# motherboard_cp2.net
KiCad netlist of a schematic drawn in EAGLE
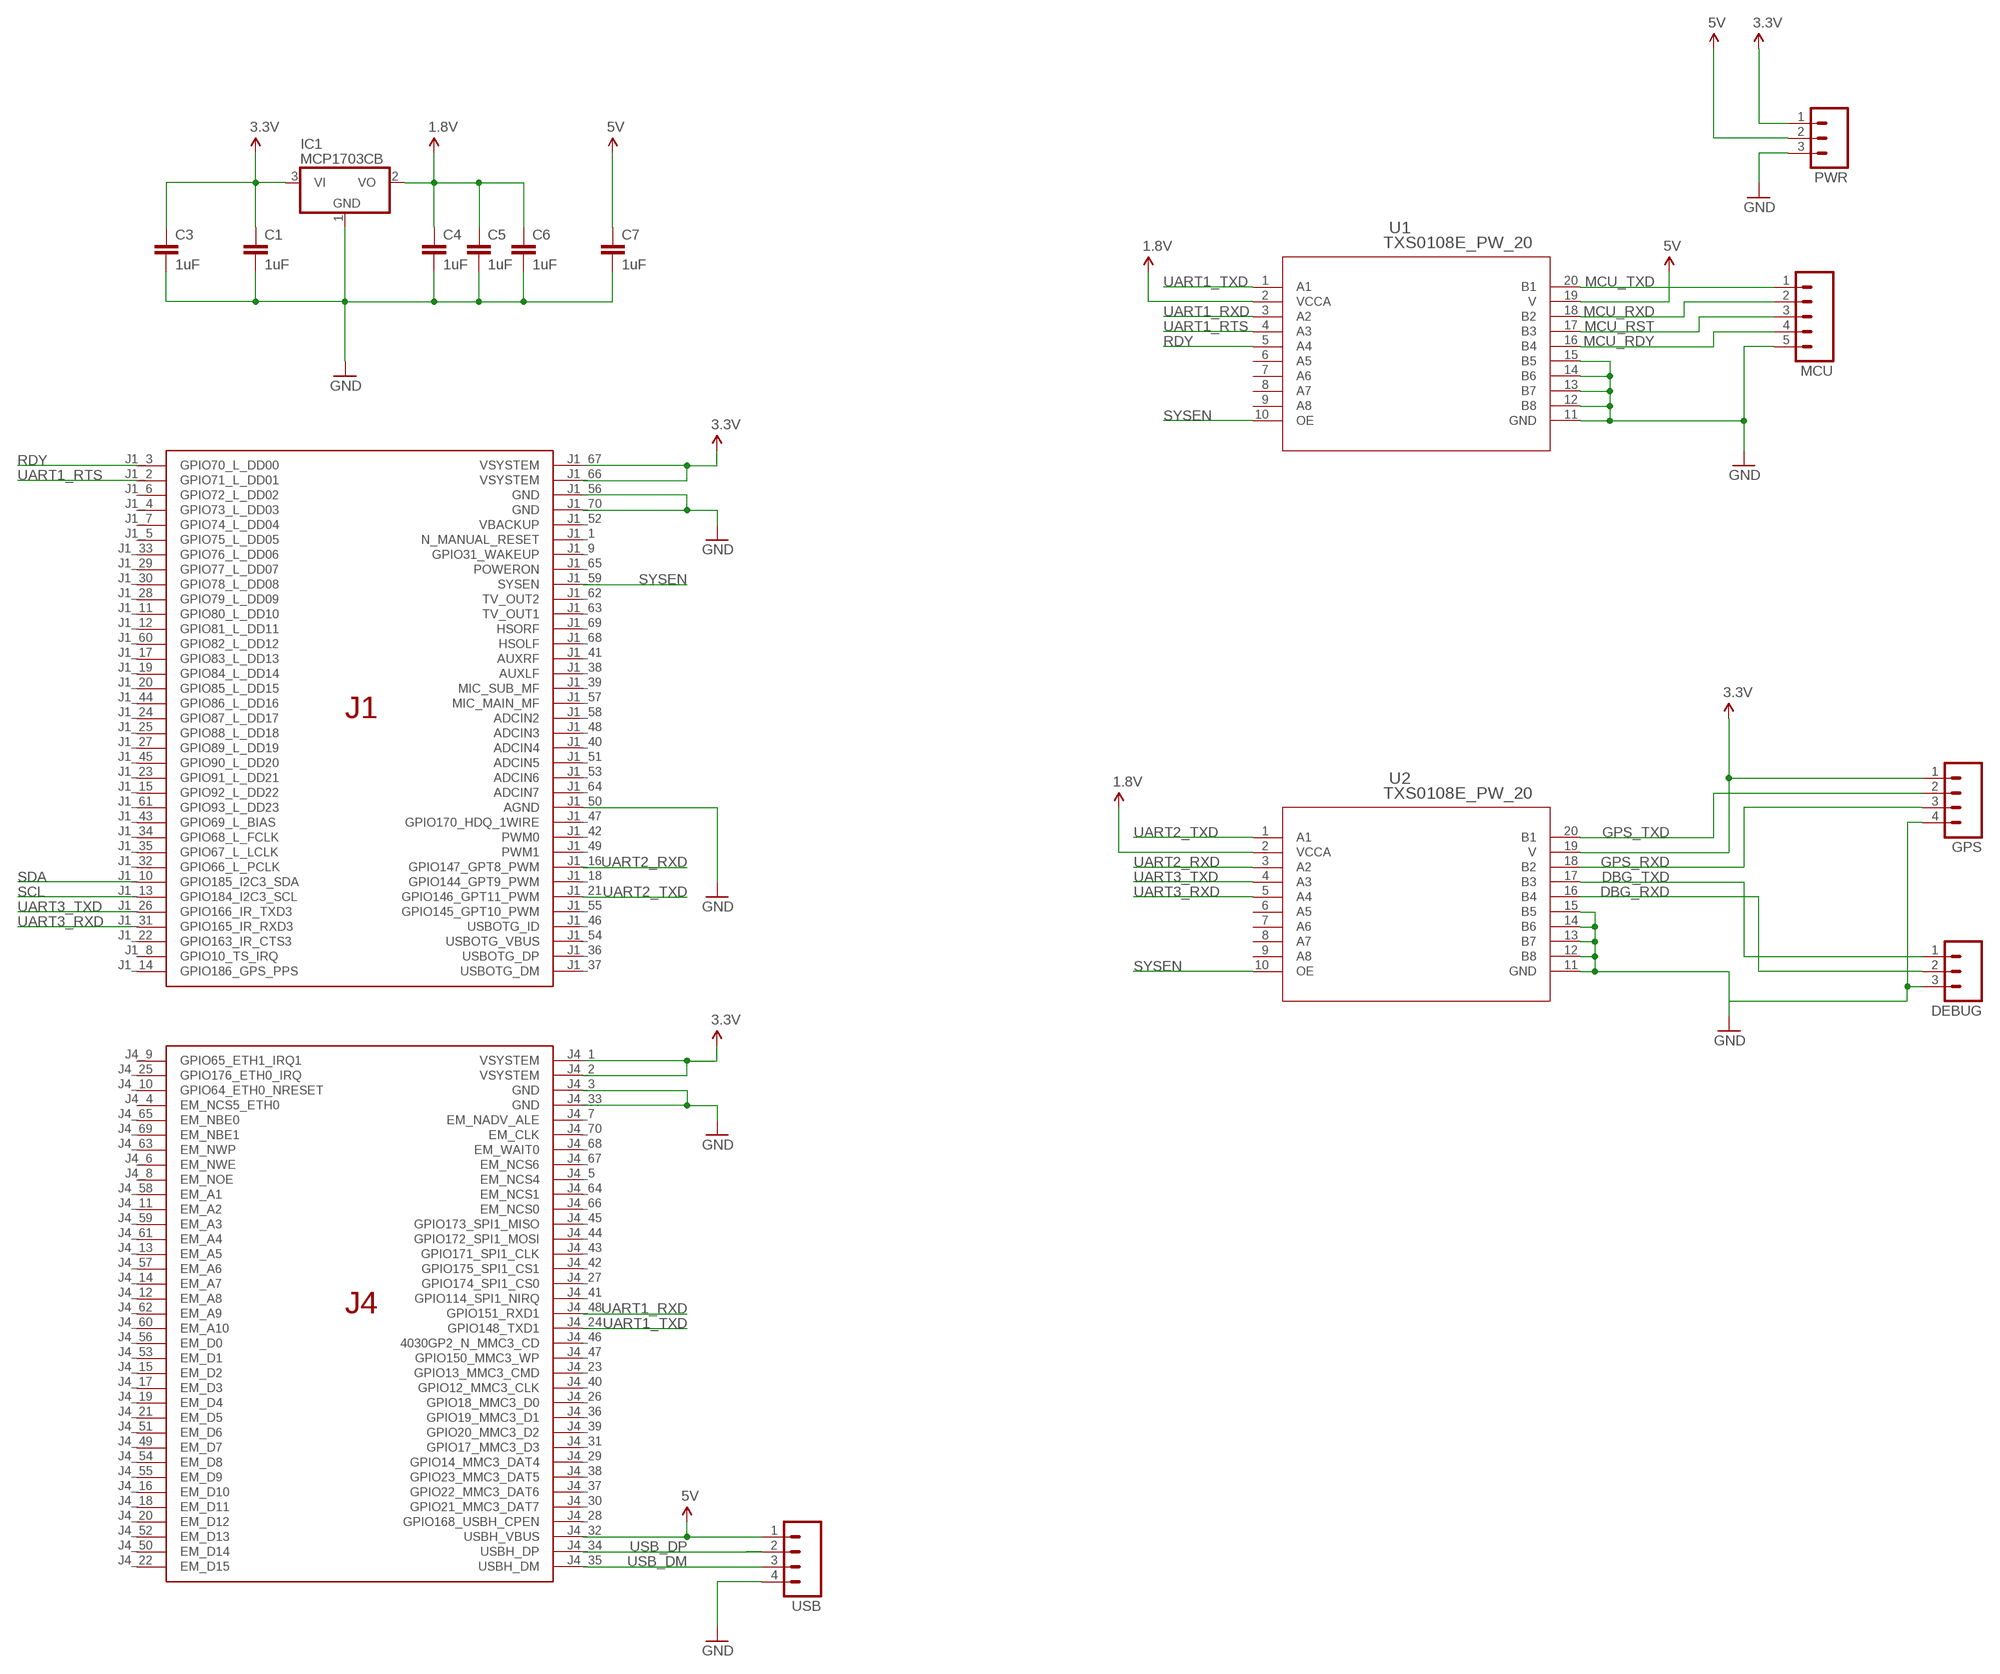
[diagram p0: schematic, sheet 1]

(export (version "E")
  (design (tool "Eeschema 10.0.6"))
  (components
    (comp (ref "C1")
      (value "1uF")
      (footprint "eagle-import:0805")
      (libsource (lib "eagle-import") (part "1UF-25V-10%(0805)"))
    )
    (comp (ref "C3")
      (value "1uF")
      (footprint "eagle-import:0805")
      (libsource (lib "eagle-import") (part "1UF-25V-10%(0805)"))
    )
    (comp (ref "C4")
      (value "1uF")
      (footprint "eagle-import:0805")
      (libsource (lib "eagle-import") (part "1UF-25V-10%(0805)"))
    )
    (comp (ref "C5")
      (value "1uF")
      (footprint "eagle-import:0805")
      (libsource (lib "eagle-import") (part "1UF-25V-10%(0805)"))
    )
    (comp (ref "C6")
      (value "1uF")
      (footprint "eagle-import:0805")
      (libsource (lib "eagle-import") (part "1UF-25V-10%(0805)"))
    )
    (comp (ref "C7")
      (value "1uF")
      (footprint "eagle-import:0805")
      (libsource (lib "eagle-import") (part "1UF-25V-10%(0805)"))
    )
    (comp (ref "DEBUG")
      (value "M03LOCK_LONGPADS")
      (footprint "eagle-import:1X03_LOCK_LONGPADS")
      (libsource (lib "eagle-import") (part "M03LOCK_LONGPADS"))
    )
    (comp (ref "GPS")
      (value "M04LONGPADS")
      (footprint "eagle-import:1X04_LONGPADS")
      (libsource (lib "eagle-import") (part "M04LONGPADS"))
    )
    (comp (ref "IC1")
      (value "MCP1703CB")
      (footprint "eagle-import:SOT23")
      (libsource (lib "eagle-import") (part "MCP1703CB"))
    )
    (comp (ref "MCU")
      (value "M05PTH_LONGPADS")
      (footprint "eagle-import:1X05_LONGPADS")
      (libsource (lib "eagle-import") (part "M05PTH_LONGPADS"))
    )
    (comp (ref "PWR")
      (value "M03LONGPADS")
      (footprint "eagle-import:1X03_LONGPADS")
      (libsource (lib "eagle-import") (part "M03LONGPADS"))
    )
    (comp (ref "U$1")
      (value "OVERO")
      (footprint "eagle-import:OVERO")
      (libsource (lib "eagle-import") (part "OVERO"))
    )
    (comp (ref "U1")
      (value "TXS0108E_PW_20")
      (footprint "eagle-import:PW20")
      (fields
        (field (name "GENERIC_PART_NUMBER") "TXS0108E")
        (field (name "MANUFACTURER") "Texas Instruments")
        (field (name "MANUFACTURER_PART_NUMBER") "txs0108e_pw_20")
      )
      (libsource (lib "eagle-import") (part "TXS0108E_PW_20"))
    )
    (comp (ref "U2")
      (value "TXS0108E_PW_20")
      (footprint "eagle-import:PW20")
      (fields
        (field (name "GENERIC_PART_NUMBER") "TXS0108E")
        (field (name "MANUFACTURER") "Texas Instruments")
        (field (name "MANUFACTURER_PART_NUMBER") "txs0108e_pw_20")
      )
      (libsource (lib "eagle-import") (part "TXS0108E_PW_20"))
    )
    (comp (ref "USB")
      (value "M04LONGPADS")
      (footprint "eagle-import:1X04_LONGPADS")
      (libsource (lib "eagle-import") (part "M04LONGPADS"))
    )
  )
  (nets
    (net (code "1") (name "/DBG_RXD") (class "Default")
      (node (ref "DEBUG") (pin "2") (pinfunction "2_2") (pintype "passive"))
      (node (ref "U2") (pin "16") (pinfunction "B4_16") (pintype "bidirectional"))
    )
    (net (code "2") (name "/DBG_TXD") (class "Default")
      (node (ref "DEBUG") (pin "1") (pinfunction "1_1") (pintype "passive"))
      (node (ref "U2") (pin "17") (pinfunction "B3_17") (pintype "bidirectional"))
    )
    (net (code "3") (name "/GPS_RXD") (class "Default")
      (node (ref "GPS") (pin "3") (pinfunction "3_3") (pintype "passive"))
      (node (ref "U2") (pin "18") (pinfunction "B2_18") (pintype "bidirectional"))
    )
    (net (code "4") (name "/GPS_TXD") (class "Default")
      (node (ref "GPS") (pin "2") (pinfunction "2_2") (pintype "passive"))
      (node (ref "U2") (pin "20") (pinfunction "B1_20") (pintype "bidirectional"))
    )
    (net (code "5") (name "/MCU_RDY") (class "Default")
      (node (ref "MCU") (pin "4") (pinfunction "4_4") (pintype "passive"))
      (node (ref "U1") (pin "16") (pinfunction "B4_16") (pintype "bidirectional"))
    )
    (net (code "6") (name "/MCU_RST") (class "Default")
      (node (ref "MCU") (pin "3") (pinfunction "3_3") (pintype "passive"))
      (node (ref "U1") (pin "17") (pinfunction "B3_17") (pintype "bidirectional"))
    )
    (net (code "7") (name "/MCU_RXD") (class "Default")
      (node (ref "MCU") (pin "2") (pinfunction "2_2") (pintype "passive"))
      (node (ref "U1") (pin "18") (pinfunction "B2_18") (pintype "bidirectional"))
    )
    (net (code "8") (name "/MCU_TXD") (class "Default")
      (node (ref "MCU") (pin "1") (pinfunction "1_1") (pintype "passive"))
      (node (ref "U1") (pin "20") (pinfunction "B1_20") (pintype "bidirectional"))
    )
    (net (code "9") (name "/RDY") (class "Default")
      (node (ref "U$1") (pin "J1_3") (pinfunction "GPIO70_L_DD00_J1_3") (pintype "bidirectional"))
      (node (ref "U1") (pin "5") (pinfunction "A4_5") (pintype "bidirectional"))
    )
    (net (code "10") (name "/SCL") (class "Default")
      (node (ref "U$1") (pin "J1_13") (pinfunction "GPIO184_I2C3_SCL_J1_13") (pintype "bidirectional"))
    )
    (net (code "11") (name "/SDA") (class "Default")
      (node (ref "U$1") (pin "J1_10") (pinfunction "GPIO185_I2C3_SDA_J1_10") (pintype "bidirectional"))
    )
    (net (code "12") (name "/SYSEN") (class "Default")
      (node (ref "U$1") (pin "J1_59") (pinfunction "SYSEN_J1_59") (pintype "bidirectional"))
      (node (ref "U1") (pin "10") (pinfunction "OE_10") (pintype "output"))
      (node (ref "U2") (pin "10") (pinfunction "OE_10") (pintype "output"))
    )
    (net (code "13") (name "/UART1_RTS") (class "Default")
      (node (ref "U$1") (pin "J1_2") (pinfunction "GPIO71_L_DD01_J1_2") (pintype "bidirectional"))
      (node (ref "U1") (pin "4") (pinfunction "A3_4") (pintype "bidirectional"))
    )
    (net (code "14") (name "/UART1_RXD") (class "Default")
      (node (ref "U$1") (pin "J4_48") (pinfunction "GPIO151_RXD1_J4_48") (pintype "bidirectional"))
      (node (ref "U1") (pin "3") (pinfunction "A2_3") (pintype "bidirectional"))
    )
    (net (code "15") (name "/UART1_TXD") (class "Default")
      (node (ref "U$1") (pin "J4_24") (pinfunction "GPIO148_TXD1_J4_24") (pintype "bidirectional"))
      (node (ref "U1") (pin "1") (pinfunction "A1_1") (pintype "bidirectional"))
    )
    (net (code "16") (name "/UART2_RXD") (class "Default")
      (node (ref "U$1") (pin "J1_16") (pinfunction "GPIO147_GPT8_PWM_J1_16") (pintype "bidirectional"))
      (node (ref "U2") (pin "3") (pinfunction "A2_3") (pintype "bidirectional"))
    )
    (net (code "17") (name "/UART2_TXD") (class "Default")
      (node (ref "U$1") (pin "J1_21") (pinfunction "GPIO146_GPT11_PWM_J1_21") (pintype "bidirectional"))
      (node (ref "U2") (pin "1") (pinfunction "A1_1") (pintype "bidirectional"))
    )
    (net (code "18") (name "/UART3_RXD") (class "Default")
      (node (ref "U$1") (pin "J1_31") (pinfunction "GPIO165_IR_RXD3_J1_31") (pintype "bidirectional"))
      (node (ref "U2") (pin "5") (pinfunction "A4_5") (pintype "bidirectional"))
    )
    (net (code "19") (name "/UART3_TXD") (class "Default")
      (node (ref "U$1") (pin "J1_26") (pinfunction "GPIO166_IR_TXD3_J1_26") (pintype "bidirectional"))
      (node (ref "U2") (pin "4") (pinfunction "A3_4") (pintype "bidirectional"))
    )
    (net (code "20") (name "/USB_DM") (class "Default")
      (node (ref "U$1") (pin "J4_35") (pinfunction "USBH_DM_J4_35") (pintype "bidirectional"))
      (node (ref "USB") (pin "3") (pinfunction "3_3") (pintype "passive"))
    )
    (net (code "21") (name "/USB_DP") (class "Default")
      (node (ref "U$1") (pin "J4_34") (pinfunction "USBH_DP_J4_34") (pintype "bidirectional"))
      (node (ref "USB") (pin "2") (pinfunction "2_2") (pintype "passive"))
    )
    (net (code "22") (name "1.8V") (class "Default")
      (node (ref "C4") (pin "1") (pinfunction "1_1") (pintype "passive"))
      (node (ref "C5") (pin "1") (pinfunction "1_1") (pintype "passive"))
      (node (ref "C6") (pin "1") (pinfunction "1_1") (pintype "passive"))
      (node (ref "IC1") (pin "2") (pinfunction "VO_2") (pintype "passive"))
      (node (ref "U1") (pin "2") (pinfunction "VCCA_2") (pintype "power_in"))
      (node (ref "U2") (pin "2") (pinfunction "VCCA_2") (pintype "power_in"))
    )
    (net (code "23") (name "3.3V") (class "Default")
      (node (ref "C1") (pin "1") (pinfunction "1_1") (pintype "passive"))
      (node (ref "C3") (pin "1") (pinfunction "1_1") (pintype "passive"))
      (node (ref "GPS") (pin "1") (pinfunction "1_1") (pintype "passive"))
      (node (ref "IC1") (pin "3") (pinfunction "VI_3") (pintype "input"))
      (node (ref "PWR") (pin "1") (pinfunction "1_1") (pintype "passive"))
      (node (ref "U$1") (pin "J1_66") (pinfunction "VSYSTEM_J1_66") (pintype "bidirectional"))
      (node (ref "U$1") (pin "J1_67") (pinfunction "VSYSTEM_J1_67") (pintype "bidirectional"))
      (node (ref "U$1") (pin "J4_1") (pinfunction "VSYSTEM_J4_1") (pintype "bidirectional"))
      (node (ref "U$1") (pin "J4_2") (pinfunction "VSYSTEM_J4_2") (pintype "bidirectional"))
      (node (ref "U2") (pin "19") (pinfunction "V_19") (pintype "power_in"))
    )
    (net (code "24") (name "5V") (class "Default")
      (node (ref "C7") (pin "1") (pinfunction "1_1") (pintype "passive"))
      (node (ref "PWR") (pin "2") (pinfunction "2_2") (pintype "passive"))
      (node (ref "U$1") (pin "J4_32") (pinfunction "USBH_VBUS_J4_32") (pintype "bidirectional"))
      (node (ref "U1") (pin "19") (pinfunction "V_19") (pintype "power_in"))
      (node (ref "USB") (pin "1") (pinfunction "1_1") (pintype "passive"))
    )
    (net (code "25") (name "GND") (class "Default")
      (node (ref "C1") (pin "2") (pinfunction "2_2") (pintype "passive"))
      (node (ref "C3") (pin "2") (pinfunction "2_2") (pintype "passive"))
      (node (ref "C4") (pin "2") (pinfunction "2_2") (pintype "passive"))
      (node (ref "C5") (pin "2") (pinfunction "2_2") (pintype "passive"))
      (node (ref "C6") (pin "2") (pinfunction "2_2") (pintype "passive"))
      (node (ref "C7") (pin "2") (pinfunction "2_2") (pintype "passive"))
      (node (ref "DEBUG") (pin "3") (pinfunction "3_3") (pintype "passive"))
      (node (ref "GPS") (pin "4") (pinfunction "4_4") (pintype "passive"))
      (node (ref "IC1") (pin "1") (pinfunction "GND_1") (pintype "passive"))
      (node (ref "MCU") (pin "5") (pinfunction "5_5") (pintype "passive"))
      (node (ref "PWR") (pin "3") (pinfunction "3_3") (pintype "passive"))
      (node (ref "U$1") (pin "J1_50") (pinfunction "AGND_J1_50") (pintype "bidirectional"))
      (node (ref "U$1") (pin "J1_56") (pinfunction "GND_J1_56") (pintype "bidirectional"))
      (node (ref "U$1") (pin "J1_70") (pinfunction "GND_J1_70") (pintype "bidirectional"))
      (node (ref "U$1") (pin "J4_3") (pinfunction "GND_J4_3") (pintype "bidirectional"))
      (node (ref "U$1") (pin "J4_33") (pinfunction "GND_J4_33") (pintype "bidirectional"))
      (node (ref "U1") (pin "11") (pinfunction "GND_11") (pintype "power_in"))
      (node (ref "U1") (pin "12") (pinfunction "B8_12") (pintype "bidirectional"))
      (node (ref "U1") (pin "13") (pinfunction "B7_13") (pintype "bidirectional"))
      (node (ref "U1") (pin "14") (pinfunction "B6_14") (pintype "bidirectional"))
      (node (ref "U1") (pin "15") (pinfunction "B5_15") (pintype "bidirectional"))
      (node (ref "U2") (pin "11") (pinfunction "GND_11") (pintype "power_in"))
      (node (ref "U2") (pin "12") (pinfunction "B8_12") (pintype "bidirectional"))
      (node (ref "U2") (pin "13") (pinfunction "B7_13") (pintype "bidirectional"))
      (node (ref "U2") (pin "14") (pinfunction "B6_14") (pintype "bidirectional"))
      (node (ref "U2") (pin "15") (pinfunction "B5_15") (pintype "bidirectional"))
      (node (ref "USB") (pin "4") (pinfunction "4_4") (pintype "passive"))
    )
    (net (code "26") (name "unconnected-(U$1-4030GP2_N_MMC3_CD-PadJ4_46)") (class "Default")
      (node (ref "U$1") (pin "J4_46") (pinfunction "4030GP2_N_MMC3_CD_J4_46") (pintype "bidirectional"))
    )
    (net (code "27") (name "unconnected-(U$1-ADCIN2-PadJ1_58)") (class "Default")
      (node (ref "U$1") (pin "J1_58") (pinfunction "ADCIN2_J1_58") (pintype "bidirectional"))
    )
    (net (code "28") (name "unconnected-(U$1-ADCIN3-PadJ1_48)") (class "Default")
      (node (ref "U$1") (pin "J1_48") (pinfunction "ADCIN3_J1_48") (pintype "bidirectional"))
    )
    (net (code "29") (name "unconnected-(U$1-ADCIN4-PadJ1_40)") (class "Default")
      (node (ref "U$1") (pin "J1_40") (pinfunction "ADCIN4_J1_40") (pintype "bidirectional"))
    )
    (net (code "30") (name "unconnected-(U$1-ADCIN5-PadJ1_51)") (class "Default")
      (node (ref "U$1") (pin "J1_51") (pinfunction "ADCIN5_J1_51") (pintype "bidirectional"))
    )
    (net (code "31") (name "unconnected-(U$1-ADCIN6-PadJ1_53)") (class "Default")
      (node (ref "U$1") (pin "J1_53") (pinfunction "ADCIN6_J1_53") (pintype "bidirectional"))
    )
    (net (code "32") (name "unconnected-(U$1-ADCIN7-PadJ1_64)") (class "Default")
      (node (ref "U$1") (pin "J1_64") (pinfunction "ADCIN7_J1_64") (pintype "bidirectional"))
    )
    (net (code "33") (name "unconnected-(U$1-AUXLF-PadJ1_38)") (class "Default")
      (node (ref "U$1") (pin "J1_38") (pinfunction "AUXLF_J1_38") (pintype "bidirectional"))
    )
    (net (code "34") (name "unconnected-(U$1-AUXRF-PadJ1_41)") (class "Default")
      (node (ref "U$1") (pin "J1_41") (pinfunction "AUXRF_J1_41") (pintype "bidirectional"))
    )
    (net (code "35") (name "unconnected-(U$1-EM_A1-PadJ4_58)") (class "Default")
      (node (ref "U$1") (pin "J4_58") (pinfunction "EM_A1_J4_58") (pintype "bidirectional"))
    )
    (net (code "36") (name "unconnected-(U$1-EM_A2-PadJ4_11)") (class "Default")
      (node (ref "U$1") (pin "J4_11") (pinfunction "EM_A2_J4_11") (pintype "bidirectional"))
    )
    (net (code "37") (name "unconnected-(U$1-EM_A3-PadJ4_59)") (class "Default")
      (node (ref "U$1") (pin "J4_59") (pinfunction "EM_A3_J4_59") (pintype "bidirectional"))
    )
    (net (code "38") (name "unconnected-(U$1-EM_A4-PadJ4_61)") (class "Default")
      (node (ref "U$1") (pin "J4_61") (pinfunction "EM_A4_J4_61") (pintype "bidirectional"))
    )
    (net (code "39") (name "unconnected-(U$1-EM_A5-PadJ4_13)") (class "Default")
      (node (ref "U$1") (pin "J4_13") (pinfunction "EM_A5_J4_13") (pintype "bidirectional"))
    )
    (net (code "40") (name "unconnected-(U$1-EM_A6-PadJ4_57)") (class "Default")
      (node (ref "U$1") (pin "J4_57") (pinfunction "EM_A6_J4_57") (pintype "bidirectional"))
    )
    (net (code "41") (name "unconnected-(U$1-EM_A7-PadJ4_14)") (class "Default")
      (node (ref "U$1") (pin "J4_14") (pinfunction "EM_A7_J4_14") (pintype "bidirectional"))
    )
    (net (code "42") (name "unconnected-(U$1-EM_A8-PadJ4_12)") (class "Default")
      (node (ref "U$1") (pin "J4_12") (pinfunction "EM_A8_J4_12") (pintype "bidirectional"))
    )
    (net (code "43") (name "unconnected-(U$1-EM_A9-PadJ4_62)") (class "Default")
      (node (ref "U$1") (pin "J4_62") (pinfunction "EM_A9_J4_62") (pintype "bidirectional"))
    )
    (net (code "44") (name "unconnected-(U$1-EM_A10-PadJ4_60)") (class "Default")
      (node (ref "U$1") (pin "J4_60") (pinfunction "EM_A10_J4_60") (pintype "bidirectional"))
    )
    (net (code "45") (name "unconnected-(U$1-EM_CLK-PadJ4_70)") (class "Default")
      (node (ref "U$1") (pin "J4_70") (pinfunction "EM_CLK_J4_70") (pintype "bidirectional"))
    )
    (net (code "46") (name "unconnected-(U$1-EM_D0-PadJ4_56)") (class "Default")
      (node (ref "U$1") (pin "J4_56") (pinfunction "EM_D0_J4_56") (pintype "bidirectional"))
    )
    (net (code "47") (name "unconnected-(U$1-EM_D1-PadJ4_53)") (class "Default")
      (node (ref "U$1") (pin "J4_53") (pinfunction "EM_D1_J4_53") (pintype "bidirectional"))
    )
    (net (code "48") (name "unconnected-(U$1-EM_D2-PadJ4_15)") (class "Default")
      (node (ref "U$1") (pin "J4_15") (pinfunction "EM_D2_J4_15") (pintype "bidirectional"))
    )
    (net (code "49") (name "unconnected-(U$1-EM_D3-PadJ4_17)") (class "Default")
      (node (ref "U$1") (pin "J4_17") (pinfunction "EM_D3_J4_17") (pintype "bidirectional"))
    )
    (net (code "50") (name "unconnected-(U$1-EM_D4-PadJ4_19)") (class "Default")
      (node (ref "U$1") (pin "J4_19") (pinfunction "EM_D4_J4_19") (pintype "bidirectional"))
    )
    (net (code "51") (name "unconnected-(U$1-EM_D5-PadJ4_21)") (class "Default")
      (node (ref "U$1") (pin "J4_21") (pinfunction "EM_D5_J4_21") (pintype "bidirectional"))
    )
    (net (code "52") (name "unconnected-(U$1-EM_D6-PadJ4_51)") (class "Default")
      (node (ref "U$1") (pin "J4_51") (pinfunction "EM_D6_J4_51") (pintype "bidirectional"))
    )
    (net (code "53") (name "unconnected-(U$1-EM_D7-PadJ4_49)") (class "Default")
      (node (ref "U$1") (pin "J4_49") (pinfunction "EM_D7_J4_49") (pintype "bidirectional"))
    )
    (net (code "54") (name "unconnected-(U$1-EM_D8-PadJ4_54)") (class "Default")
      (node (ref "U$1") (pin "J4_54") (pinfunction "EM_D8_J4_54") (pintype "bidirectional"))
    )
    (net (code "55") (name "unconnected-(U$1-EM_D9-PadJ4_55)") (class "Default")
      (node (ref "U$1") (pin "J4_55") (pinfunction "EM_D9_J4_55") (pintype "bidirectional"))
    )
    (net (code "56") (name "unconnected-(U$1-EM_D10-PadJ4_16)") (class "Default")
      (node (ref "U$1") (pin "J4_16") (pinfunction "EM_D10_J4_16") (pintype "bidirectional"))
    )
    (net (code "57") (name "unconnected-(U$1-EM_D11-PadJ4_18)") (class "Default")
      (node (ref "U$1") (pin "J4_18") (pinfunction "EM_D11_J4_18") (pintype "bidirectional"))
    )
    (net (code "58") (name "unconnected-(U$1-EM_D12-PadJ4_20)") (class "Default")
      (node (ref "U$1") (pin "J4_20") (pinfunction "EM_D12_J4_20") (pintype "bidirectional"))
    )
    (net (code "59") (name "unconnected-(U$1-EM_D13-PadJ4_52)") (class "Default")
      (node (ref "U$1") (pin "J4_52") (pinfunction "EM_D13_J4_52") (pintype "bidirectional"))
    )
    (net (code "60") (name "unconnected-(U$1-EM_D14-PadJ4_50)") (class "Default")
      (node (ref "U$1") (pin "J4_50") (pinfunction "EM_D14_J4_50") (pintype "bidirectional"))
    )
    (net (code "61") (name "unconnected-(U$1-EM_D15-PadJ4_22)") (class "Default")
      (node (ref "U$1") (pin "J4_22") (pinfunction "EM_D15_J4_22") (pintype "bidirectional"))
    )
    (net (code "62") (name "unconnected-(U$1-EM_NADV_ALE-PadJ4_7)") (class "Default")
      (node (ref "U$1") (pin "J4_7") (pinfunction "EM_NADV_ALE_J4_7") (pintype "bidirectional"))
    )
    (net (code "63") (name "unconnected-(U$1-EM_NBE0-PadJ4_65)") (class "Default")
      (node (ref "U$1") (pin "J4_65") (pinfunction "EM_NBE0_J4_65") (pintype "bidirectional"))
    )
    (net (code "64") (name "unconnected-(U$1-EM_NBE1-PadJ4_69)") (class "Default")
      (node (ref "U$1") (pin "J4_69") (pinfunction "EM_NBE1_J4_69") (pintype "bidirectional"))
    )
    (net (code "65") (name "unconnected-(U$1-EM_NCS0-PadJ4_66)") (class "Default")
      (node (ref "U$1") (pin "J4_66") (pinfunction "EM_NCS0_J4_66") (pintype "bidirectional"))
    )
    (net (code "66") (name "unconnected-(U$1-EM_NCS1-PadJ4_64)") (class "Default")
      (node (ref "U$1") (pin "J4_64") (pinfunction "EM_NCS1_J4_64") (pintype "bidirectional"))
    )
    (net (code "67") (name "unconnected-(U$1-EM_NCS4-PadJ4_5)") (class "Default")
      (node (ref "U$1") (pin "J4_5") (pinfunction "EM_NCS4_J4_5") (pintype "bidirectional"))
    )
    (net (code "68") (name "unconnected-(U$1-EM_NCS5_ETH0-PadJ4_4)") (class "Default")
      (node (ref "U$1") (pin "J4_4") (pinfunction "EM_NCS5_ETH0_J4_4") (pintype "bidirectional"))
    )
    (net (code "69") (name "unconnected-(U$1-EM_NCS6-PadJ4_67)") (class "Default")
      (node (ref "U$1") (pin "J4_67") (pinfunction "EM_NCS6_J4_67") (pintype "bidirectional"))
    )
    (net (code "70") (name "unconnected-(U$1-EM_NOE-PadJ4_8)") (class "Default")
      (node (ref "U$1") (pin "J4_8") (pinfunction "EM_NOE_J4_8") (pintype "bidirectional"))
    )
    (net (code "71") (name "unconnected-(U$1-EM_NWE-PadJ4_6)") (class "Default")
      (node (ref "U$1") (pin "J4_6") (pinfunction "EM_NWE_J4_6") (pintype "bidirectional"))
    )
    (net (code "72") (name "unconnected-(U$1-EM_NWP-PadJ4_63)") (class "Default")
      (node (ref "U$1") (pin "J4_63") (pinfunction "EM_NWP_J4_63") (pintype "bidirectional"))
    )
    (net (code "73") (name "unconnected-(U$1-EM_WAIT0-PadJ4_68)") (class "Default")
      (node (ref "U$1") (pin "J4_68") (pinfunction "EM_WAIT0_J4_68") (pintype "bidirectional"))
    )
    (net (code "74") (name "unconnected-(U$1-GPIO10_TS_IRQ-PadJ1_8)") (class "Default")
      (node (ref "U$1") (pin "J1_8") (pinfunction "GPIO10_TS_IRQ_J1_8") (pintype "bidirectional"))
    )
    (net (code "75") (name "unconnected-(U$1-GPIO12_MMC3_CLK-PadJ4_40)") (class "Default")
      (node (ref "U$1") (pin "J4_40") (pinfunction "GPIO12_MMC3_CLK_J4_40") (pintype "bidirectional"))
    )
    (net (code "76") (name "unconnected-(U$1-GPIO13_MMC3_CMD-PadJ4_23)") (class "Default")
      (node (ref "U$1") (pin "J4_23") (pinfunction "GPIO13_MMC3_CMD_J4_23") (pintype "bidirectional"))
    )
    (net (code "77") (name "unconnected-(U$1-GPIO14_MMC3_DAT4-PadJ4_29)") (class "Default")
      (node (ref "U$1") (pin "J4_29") (pinfunction "GPIO14_MMC3_DAT4_J4_29") (pintype "bidirectional"))
    )
    (net (code "78") (name "unconnected-(U$1-GPIO17_MMC3_D3-PadJ4_31)") (class "Default")
      (node (ref "U$1") (pin "J4_31") (pinfunction "GPIO17_MMC3_D3_J4_31") (pintype "bidirectional"))
    )
    (net (code "79") (name "unconnected-(U$1-GPIO18_MMC3_D0-PadJ4_26)") (class "Default")
      (node (ref "U$1") (pin "J4_26") (pinfunction "GPIO18_MMC3_D0_J4_26") (pintype "bidirectional"))
    )
    (net (code "80") (name "unconnected-(U$1-GPIO19_MMC3_D1-PadJ4_36)") (class "Default")
      (node (ref "U$1") (pin "J4_36") (pinfunction "GPIO19_MMC3_D1_J4_36") (pintype "bidirectional"))
    )
    (net (code "81") (name "unconnected-(U$1-GPIO20_MMC3_D2-PadJ4_39)") (class "Default")
      (node (ref "U$1") (pin "J4_39") (pinfunction "GPIO20_MMC3_D2_J4_39") (pintype "bidirectional"))
    )
    (net (code "82") (name "unconnected-(U$1-GPIO21_MMC3_DAT7-PadJ4_30)") (class "Default")
      (node (ref "U$1") (pin "J4_30") (pinfunction "GPIO21_MMC3_DAT7_J4_30") (pintype "bidirectional"))
    )
    (net (code "83") (name "unconnected-(U$1-GPIO22_MMC3_DAT6-PadJ4_37)") (class "Default")
      (node (ref "U$1") (pin "J4_37") (pinfunction "GPIO22_MMC3_DAT6_J4_37") (pintype "bidirectional"))
    )
    (net (code "84") (name "unconnected-(U$1-GPIO23_MMC3_DAT5-PadJ4_38)") (class "Default")
      (node (ref "U$1") (pin "J4_38") (pinfunction "GPIO23_MMC3_DAT5_J4_38") (pintype "bidirectional"))
    )
    (net (code "85") (name "unconnected-(U$1-GPIO31_WAKEUP-PadJ1_9)") (class "Default")
      (node (ref "U$1") (pin "J1_9") (pinfunction "GPIO31_WAKEUP_J1_9") (pintype "bidirectional"))
    )
    (net (code "86") (name "unconnected-(U$1-GPIO64_ETH0_NRESET-PadJ4_10)") (class "Default")
      (node (ref "U$1") (pin "J4_10") (pinfunction "GPIO64_ETH0_NRESET_J4_10") (pintype "bidirectional"))
    )
    (net (code "87") (name "unconnected-(U$1-GPIO65_ETH1_IRQ1-PadJ4_9)") (class "Default")
      (node (ref "U$1") (pin "J4_9") (pinfunction "GPIO65_ETH1_IRQ1_J4_9") (pintype "bidirectional"))
    )
    (net (code "88") (name "unconnected-(U$1-GPIO66_L_PCLK-PadJ1_32)") (class "Default")
      (node (ref "U$1") (pin "J1_32") (pinfunction "GPIO66_L_PCLK_J1_32") (pintype "bidirectional"))
    )
    (net (code "89") (name "unconnected-(U$1-GPIO67_L_LCLK-PadJ1_35)") (class "Default")
      (node (ref "U$1") (pin "J1_35") (pinfunction "GPIO67_L_LCLK_J1_35") (pintype "bidirectional"))
    )
    (net (code "90") (name "unconnected-(U$1-GPIO68_L_FCLK-PadJ1_34)") (class "Default")
      (node (ref "U$1") (pin "J1_34") (pinfunction "GPIO68_L_FCLK_J1_34") (pintype "bidirectional"))
    )
    (net (code "91") (name "unconnected-(U$1-GPIO69_L_BIAS-PadJ1_43)") (class "Default")
      (node (ref "U$1") (pin "J1_43") (pinfunction "GPIO69_L_BIAS_J1_43") (pintype "bidirectional"))
    )
    (net (code "92") (name "unconnected-(U$1-GPIO72_L_DD02-PadJ1_6)") (class "Default")
      (node (ref "U$1") (pin "J1_6") (pinfunction "GPIO72_L_DD02_J1_6") (pintype "bidirectional"))
    )
    (net (code "93") (name "unconnected-(U$1-GPIO73_L_DD03-PadJ1_4)") (class "Default")
      (node (ref "U$1") (pin "J1_4") (pinfunction "GPIO73_L_DD03_J1_4") (pintype "bidirectional"))
    )
    (net (code "94") (name "unconnected-(U$1-GPIO74_L_DD04-PadJ1_7)") (class "Default")
      (node (ref "U$1") (pin "J1_7") (pinfunction "GPIO74_L_DD04_J1_7") (pintype "bidirectional"))
    )
    (net (code "95") (name "unconnected-(U$1-GPIO75_L_DD05-PadJ1_5)") (class "Default")
      (node (ref "U$1") (pin "J1_5") (pinfunction "GPIO75_L_DD05_J1_5") (pintype "bidirectional"))
    )
    (net (code "96") (name "unconnected-(U$1-GPIO76_L_DD06-PadJ1_33)") (class "Default")
      (node (ref "U$1") (pin "J1_33") (pinfunction "GPIO76_L_DD06_J1_33") (pintype "bidirectional"))
    )
    (net (code "97") (name "unconnected-(U$1-GPIO77_L_DD07-PadJ1_29)") (class "Default")
      (node (ref "U$1") (pin "J1_29") (pinfunction "GPIO77_L_DD07_J1_29") (pintype "bidirectional"))
    )
    (net (code "98") (name "unconnected-(U$1-GPIO78_L_DD08-PadJ1_30)") (class "Default")
      (node (ref "U$1") (pin "J1_30") (pinfunction "GPIO78_L_DD08_J1_30") (pintype "bidirectional"))
    )
    (net (code "99") (name "unconnected-(U$1-GPIO79_L_DD09-PadJ1_28)") (class "Default")
      (node (ref "U$1") (pin "J1_28") (pinfunction "GPIO79_L_DD09_J1_28") (pintype "bidirectional"))
    )
    (net (code "100") (name "unconnected-(U$1-GPIO80_L_DD10-PadJ1_11)") (class "Default")
      (node (ref "U$1") (pin "J1_11") (pinfunction "GPIO80_L_DD10_J1_11") (pintype "bidirectional"))
    )
    (net (code "101") (name "unconnected-(U$1-GPIO81_L_DD11-PadJ1_12)") (class "Default")
      (node (ref "U$1") (pin "J1_12") (pinfunction "GPIO81_L_DD11_J1_12") (pintype "bidirectional"))
    )
    (net (code "102") (name "unconnected-(U$1-GPIO82_L_DD12-PadJ1_60)") (class "Default")
      (node (ref "U$1") (pin "J1_60") (pinfunction "GPIO82_L_DD12_J1_60") (pintype "bidirectional"))
    )
    (net (code "103") (name "unconnected-(U$1-GPIO83_L_DD13-PadJ1_17)") (class "Default")
      (node (ref "U$1") (pin "J1_17") (pinfunction "GPIO83_L_DD13_J1_17") (pintype "bidirectional"))
    )
    (net (code "104") (name "unconnected-(U$1-GPIO84_L_DD14-PadJ1_19)") (class "Default")
      (node (ref "U$1") (pin "J1_19") (pinfunction "GPIO84_L_DD14_J1_19") (pintype "bidirectional"))
    )
    (net (code "105") (name "unconnected-(U$1-GPIO85_L_DD15-PadJ1_20)") (class "Default")
      (node (ref "U$1") (pin "J1_20") (pinfunction "GPIO85_L_DD15_J1_20") (pintype "bidirectional"))
    )
    (net (code "106") (name "unconnected-(U$1-GPIO86_L_DD16-PadJ1_44)") (class "Default")
      (node (ref "U$1") (pin "J1_44") (pinfunction "GPIO86_L_DD16_J1_44") (pintype "bidirectional"))
    )
    (net (code "107") (name "unconnected-(U$1-GPIO87_L_DD17-PadJ1_24)") (class "Default")
      (node (ref "U$1") (pin "J1_24") (pinfunction "GPIO87_L_DD17_J1_24") (pintype "bidirectional"))
    )
    (net (code "108") (name "unconnected-(U$1-GPIO88_L_DD18-PadJ1_25)") (class "Default")
      (node (ref "U$1") (pin "J1_25") (pinfunction "GPIO88_L_DD18_J1_25") (pintype "bidirectional"))
    )
    (net (code "109") (name "unconnected-(U$1-GPIO89_L_DD19-PadJ1_27)") (class "Default")
      (node (ref "U$1") (pin "J1_27") (pinfunction "GPIO89_L_DD19_J1_27") (pintype "bidirectional"))
    )
    (net (code "110") (name "unconnected-(U$1-GPIO90_L_DD20-PadJ1_45)") (class "Default")
      (node (ref "U$1") (pin "J1_45") (pinfunction "GPIO90_L_DD20_J1_45") (pintype "bidirectional"))
    )
    (net (code "111") (name "unconnected-(U$1-GPIO91_L_DD21-PadJ1_23)") (class "Default")
      (node (ref "U$1") (pin "J1_23") (pinfunction "GPIO91_L_DD21_J1_23") (pintype "bidirectional"))
    )
    (net (code "112") (name "unconnected-(U$1-GPIO92_L_DD22-PadJ1_15)") (class "Default")
      (node (ref "U$1") (pin "J1_15") (pinfunction "GPIO92_L_DD22_J1_15") (pintype "bidirectional"))
    )
    (net (code "113") (name "unconnected-(U$1-GPIO93_L_DD23-PadJ1_61)") (class "Default")
      (node (ref "U$1") (pin "J1_61") (pinfunction "GPIO93_L_DD23_J1_61") (pintype "bidirectional"))
    )
    (net (code "114") (name "unconnected-(U$1-GPIO114_SPI1_NIRQ-PadJ4_41)") (class "Default")
      (node (ref "U$1") (pin "J4_41") (pinfunction "GPIO114_SPI1_NIRQ_J4_41") (pintype "bidirectional"))
    )
    (net (code "115") (name "unconnected-(U$1-GPIO144_GPT9_PWM-PadJ1_18)") (class "Default")
      (node (ref "U$1") (pin "J1_18") (pinfunction "GPIO144_GPT9_PWM_J1_18") (pintype "bidirectional"))
    )
    (net (code "116") (name "unconnected-(U$1-GPIO145_GPT10_PWM-PadJ1_55)") (class "Default")
      (node (ref "U$1") (pin "J1_55") (pinfunction "GPIO145_GPT10_PWM_J1_55") (pintype "bidirectional"))
    )
    (net (code "117") (name "unconnected-(U$1-GPIO150_MMC3_WP-PadJ4_47)") (class "Default")
      (node (ref "U$1") (pin "J4_47") (pinfunction "GPIO150_MMC3_WP_J4_47") (pintype "bidirectional"))
    )
    (net (code "118") (name "unconnected-(U$1-GPIO163_IR_CTS3-PadJ1_22)") (class "Default")
      (node (ref "U$1") (pin "J1_22") (pinfunction "GPIO163_IR_CTS3_J1_22") (pintype "bidirectional"))
    )
    (net (code "119") (name "unconnected-(U$1-GPIO168_USBH_CPEN-PadJ4_28)") (class "Default")
      (node (ref "U$1") (pin "J4_28") (pinfunction "GPIO168_USBH_CPEN_J4_28") (pintype "bidirectional"))
    )
    (net (code "120") (name "unconnected-(U$1-GPIO170_HDQ_1WIRE-PadJ1_47)") (class "Default")
      (node (ref "U$1") (pin "J1_47") (pinfunction "GPIO170_HDQ_1WIRE_J1_47") (pintype "bidirectional"))
    )
    (net (code "121") (name "unconnected-(U$1-GPIO171_SPI1_CLK-PadJ4_43)") (class "Default")
      (node (ref "U$1") (pin "J4_43") (pinfunction "GPIO171_SPI1_CLK_J4_43") (pintype "bidirectional"))
    )
    (net (code "122") (name "unconnected-(U$1-GPIO172_SPI1_MOSI-PadJ4_44)") (class "Default")
      (node (ref "U$1") (pin "J4_44") (pinfunction "GPIO172_SPI1_MOSI_J4_44") (pintype "bidirectional"))
    )
    (net (code "123") (name "unconnected-(U$1-GPIO173_SPI1_MISO-PadJ4_45)") (class "Default")
      (node (ref "U$1") (pin "J4_45") (pinfunction "GPIO173_SPI1_MISO_J4_45") (pintype "bidirectional"))
    )
    (net (code "124") (name "unconnected-(U$1-GPIO174_SPI1_CS0-PadJ4_27)") (class "Default")
      (node (ref "U$1") (pin "J4_27") (pinfunction "GPIO174_SPI1_CS0_J4_27") (pintype "bidirectional"))
    )
    (net (code "125") (name "unconnected-(U$1-GPIO175_SPI1_CS1-PadJ4_42)") (class "Default")
      (node (ref "U$1") (pin "J4_42") (pinfunction "GPIO175_SPI1_CS1_J4_42") (pintype "bidirectional"))
    )
    (net (code "126") (name "unconnected-(U$1-GPIO176_ETH0_IRQ-PadJ4_25)") (class "Default")
      (node (ref "U$1") (pin "J4_25") (pinfunction "GPIO176_ETH0_IRQ_J4_25") (pintype "bidirectional"))
    )
    (net (code "127") (name "unconnected-(U$1-GPIO186_GPS_PPS-PadJ1_14)") (class "Default")
      (node (ref "U$1") (pin "J1_14") (pinfunction "GPIO186_GPS_PPS_J1_14") (pintype "bidirectional"))
    )
    (net (code "128") (name "unconnected-(U$1-HSOLF-PadJ1_68)") (class "Default")
      (node (ref "U$1") (pin "J1_68") (pinfunction "HSOLF_J1_68") (pintype "bidirectional"))
    )
    (net (code "129") (name "unconnected-(U$1-HSORF-PadJ1_69)") (class "Default")
      (node (ref "U$1") (pin "J1_69") (pinfunction "HSORF_J1_69") (pintype "bidirectional"))
    )
    (net (code "130") (name "unconnected-(U$1-MIC_MAIN_MF-PadJ1_57)") (class "Default")
      (node (ref "U$1") (pin "J1_57") (pinfunction "MIC_MAIN_MF_J1_57") (pintype "bidirectional"))
    )
    (net (code "131") (name "unconnected-(U$1-MIC_SUB_MF-PadJ1_39)") (class "Default")
      (node (ref "U$1") (pin "J1_39") (pinfunction "MIC_SUB_MF_J1_39") (pintype "bidirectional"))
    )
    (net (code "132") (name "unconnected-(U$1-N_MANUAL_RESET-PadJ1_1)") (class "Default")
      (node (ref "U$1") (pin "J1_1") (pinfunction "N_MANUAL_RESET_J1_1") (pintype "bidirectional"))
    )
    (net (code "133") (name "unconnected-(U$1-POWERON-PadJ1_65)") (class "Default")
      (node (ref "U$1") (pin "J1_65") (pinfunction "POWERON_J1_65") (pintype "bidirectional"))
    )
    (net (code "134") (name "unconnected-(U$1-PWM0-PadJ1_42)") (class "Default")
      (node (ref "U$1") (pin "J1_42") (pinfunction "PWM0_J1_42") (pintype "bidirectional"))
    )
    (net (code "135") (name "unconnected-(U$1-PWM1-PadJ1_49)") (class "Default")
      (node (ref "U$1") (pin "J1_49") (pinfunction "PWM1_J1_49") (pintype "bidirectional"))
    )
    (net (code "136") (name "unconnected-(U$1-TV_OUT1-PadJ1_63)") (class "Default")
      (node (ref "U$1") (pin "J1_63") (pinfunction "TV_OUT1_J1_63") (pintype "bidirectional"))
    )
    (net (code "137") (name "unconnected-(U$1-TV_OUT2-PadJ1_62)") (class "Default")
      (node (ref "U$1") (pin "J1_62") (pinfunction "TV_OUT2_J1_62") (pintype "bidirectional"))
    )
    (net (code "138") (name "unconnected-(U$1-USBOTG_DM-PadJ1_37)") (class "Default")
      (node (ref "U$1") (pin "J1_37") (pinfunction "USBOTG_DM_J1_37") (pintype "bidirectional"))
    )
    (net (code "139") (name "unconnected-(U$1-USBOTG_DP-PadJ1_36)") (class "Default")
      (node (ref "U$1") (pin "J1_36") (pinfunction "USBOTG_DP_J1_36") (pintype "bidirectional"))
    )
    (net (code "140") (name "unconnected-(U$1-USBOTG_ID-PadJ1_46)") (class "Default")
      (node (ref "U$1") (pin "J1_46") (pinfunction "USBOTG_ID_J1_46") (pintype "bidirectional"))
    )
    (net (code "141") (name "unconnected-(U$1-USBOTG_VBUS-PadJ1_54)") (class "Default")
      (node (ref "U$1") (pin "J1_54") (pinfunction "USBOTG_VBUS_J1_54") (pintype "bidirectional"))
    )
    (net (code "142") (name "unconnected-(U$1-VBACKUP-PadJ1_52)") (class "Default")
      (node (ref "U$1") (pin "J1_52") (pinfunction "VBACKUP_J1_52") (pintype "bidirectional"))
    )
    (net (code "143") (name "unconnected-(U1-A5-Pad6)") (class "Default")
      (node (ref "U1") (pin "6") (pinfunction "A5_6") (pintype "bidirectional"))
    )
    (net (code "144") (name "unconnected-(U1-A6-Pad7)") (class "Default")
      (node (ref "U1") (pin "7") (pinfunction "A6_7") (pintype "bidirectional"))
    )
    (net (code "145") (name "unconnected-(U1-A7-Pad8)") (class "Default")
      (node (ref "U1") (pin "8") (pinfunction "A7_8") (pintype "bidirectional"))
    )
    (net (code "146") (name "unconnected-(U1-A8-Pad9)") (class "Default")
      (node (ref "U1") (pin "9") (pinfunction "A8_9") (pintype "bidirectional"))
    )
    (net (code "147") (name "unconnected-(U2-A5-Pad6)") (class "Default")
      (node (ref "U2") (pin "6") (pinfunction "A5_6") (pintype "bidirectional"))
    )
    (net (code "148") (name "unconnected-(U2-A6-Pad7)") (class "Default")
      (node (ref "U2") (pin "7") (pinfunction "A6_7") (pintype "bidirectional"))
    )
    (net (code "149") (name "unconnected-(U2-A7-Pad8)") (class "Default")
      (node (ref "U2") (pin "8") (pinfunction "A7_8") (pintype "bidirectional"))
    )
    (net (code "150") (name "unconnected-(U2-A8-Pad9)") (class "Default")
      (node (ref "U2") (pin "9") (pinfunction "A8_9") (pintype "bidirectional"))
    )
  )
)
